# MCU.net
KiCad netlist of a schematic drawn in Altium Designer
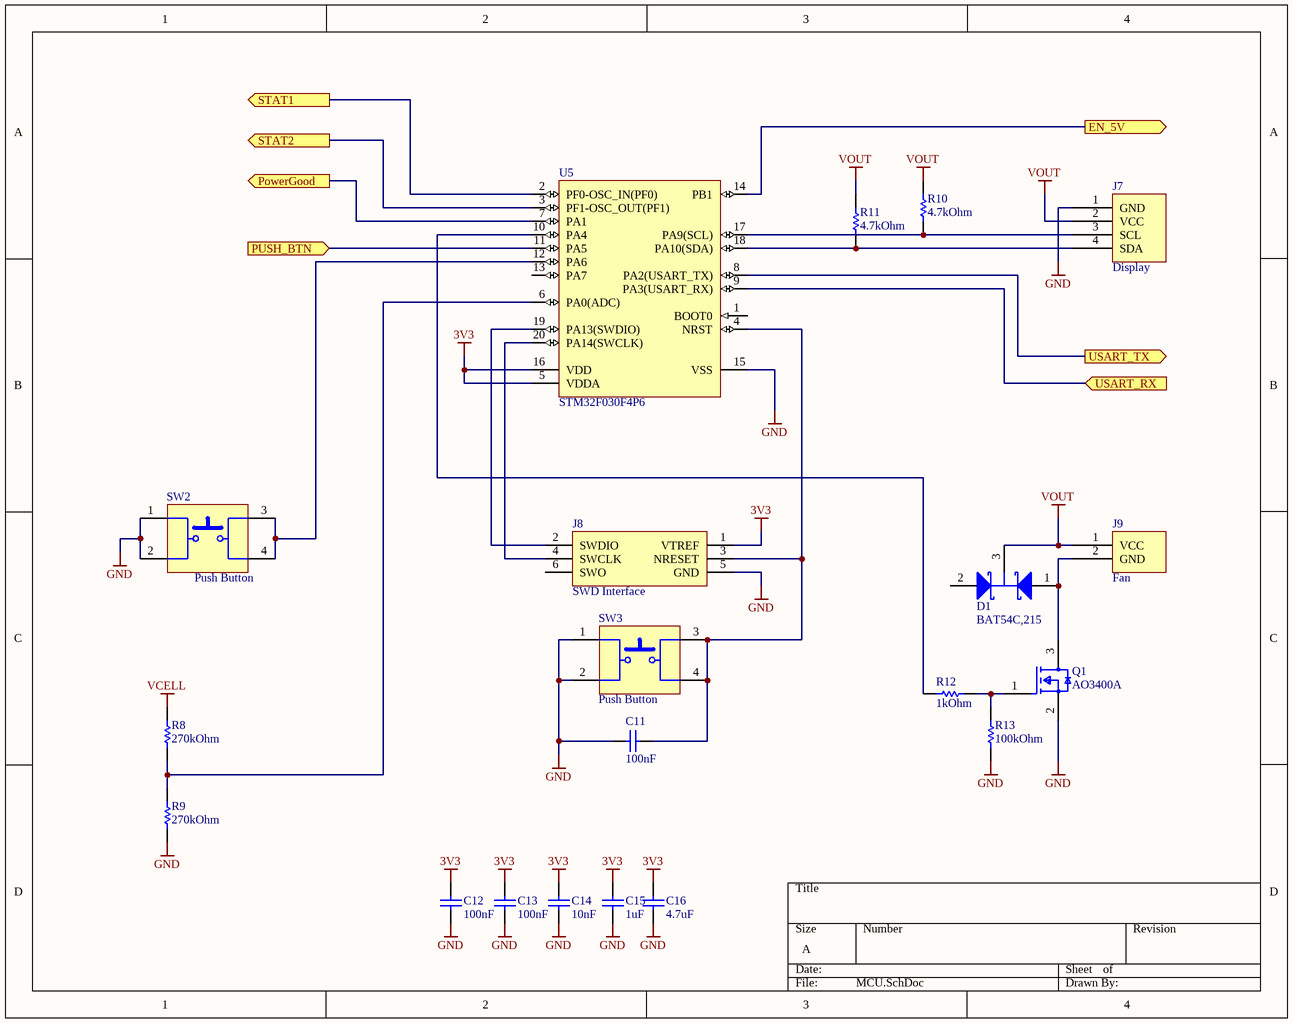
[diagram p0: MCU.SchDoc]

(export (version "E")
  (design (tool "Eeschema 10.0.6"))
  (components
    (comp (ref "C11")
      (value "100nF")
      (footprint "CAP_0804")
      (fields
        (field (name "TOLERANCE") "10%")
        (field (name "PARTNUMBER") "1206GC102KAT1A")
        (field (name "MANUFACTURER") "AVX")
      )
      (libsource (lib "Schlib") (part "CAP_100NF"))
    )
    (comp (ref "C12")
      (value "100nF")
      (footprint "CAP_0804")
      (fields
        (field (name "TOLERANCE") "10%")
        (field (name "PARTNUMBER") "1206GC102KAT1A")
        (field (name "MANUFACTURER") "AVX")
      )
      (libsource (lib "Schlib") (part "CAP_100NF"))
    )
    (comp (ref "C13")
      (value "100nF")
      (footprint "CAP_0804")
      (fields
        (field (name "TOLERANCE") "10%")
        (field (name "PARTNUMBER") "1206GC102KAT1A")
        (field (name "MANUFACTURER") "AVX")
      )
      (libsource (lib "Schlib") (part "CAP_100NF"))
    )
    (comp (ref "C14")
      (value "10nF")
      (footprint "CAP_0804")
      (fields
        (field (name "TOLERANCE") "10%")
        (field (name "PARTNUMBER") "1206GC102KAT1A")
        (field (name "MANUFACTURER") "AVX")
      )
      (libsource (lib "Schlib") (part "CAP_10NF"))
    )
    (comp (ref "C15")
      (value "1uF")
      (footprint "CAP_0804")
      (fields
        (field (name "TOLERANCE") "10%")
        (field (name "PARTNUMBER") "1206GC102KAT1A")
        (field (name "MANUFACTURER") "AVX")
      )
      (libsource (lib "Schlib") (part "CAP_1UF"))
    )
    (comp (ref "C16")
      (value "4.7uF")
      (footprint "CAP_0804")
      (fields
        (field (name "TOLERANCE") "10%")
        (field (name "PARTNUMBER") "1206GC102KAT1A")
        (field (name "MANUFACTURER") "AVX")
      )
      (libsource (lib "Schlib") (part "CAP_4.7UF"))
    )
    (comp (ref "D1")
      (value "BAT54C,215")
      (footprint "SOT23")
      (description "Schottky Barrier Diode, 30 V, 3-Pin SOT23, RoHS, Tape and Reel")
      (fields (field (name "MANUFACTURER") "NXP Semiconductors"))
      (libsource (lib "Schlib") (part "DIODE_BAT54C"))
    )
    (comp (ref "J7")
      (value "Display")
      (footprint "OLED_DISPLAY")
      (fields (field (name "MANUFACTURER") "Samtec") (field (name "PARTNUMBER") "MMS-104-01-T-SV"))
      (libsource (lib "Schlib") (part "Oled Display"))
    )
    (comp (ref "J8")
      (value "SWD Interface")
      (footprint "J-Link_6-pin_Needle_Adapter")
      (description "J-Link 6-pin Needle Adapter")
      (libsource (lib "Schlib") (part "J-Link_6-pin_Needle_Adapter"))
    )
    (comp (ref "J9")
      (value "Fan")
      (footprint "FAN_CONNECTOR")
      (fields (field (name "MANUFACTURER") "Samtec") (field (name "PARTNUMBER") "MMS-104-01-T-SV"))
      (libsource (lib "Schlib") (part "FAN"))
    )
    (comp (ref "Q1")
      (value "AO3400A")
      (footprint "SOT23")
      (description "MOSFET N-CH 30V 5.7A SOT23")
      (libsource (lib "Schlib") (part "MOSFET_AO3400A"))
    )
    (comp (ref "R8")
      (value "270kOhm")
      (footprint "RES_0804")
      (fields (field (name "PART NUMBER") "CRCW120647K0FKEA") (field (name "MANUFACTURER") "Vishay Dale"))
      (libsource (lib "Schlib") (part "RES_270K"))
    )
    (comp (ref "R9")
      (value "270kOhm")
      (footprint "RES_0804")
      (fields (field (name "PART NUMBER") "CRCW120647K0FKEA") (field (name "MANUFACTURER") "Vishay Dale"))
      (libsource (lib "Schlib") (part "RES_270K"))
    )
    (comp (ref "R10")
      (value "4.7kOhm")
      (footprint "RES_0804")
      (fields (field (name "PART NUMBER") "CRCW120647K0FKEA") (field (name "MANUFACTURER") "Vishay Dale"))
      (libsource (lib "Schlib") (part "RES_4.7K"))
    )
    (comp (ref "R11")
      (value "4.7kOhm")
      (footprint "RES_0804")
      (fields (field (name "PART NUMBER") "CRCW120647K0FKEA") (field (name "MANUFACTURER") "Vishay Dale"))
      (libsource (lib "Schlib") (part "RES_4.7K"))
    )
    (comp (ref "R12")
      (value "1kOhm")
      (footprint "RES_0804")
      (fields (field (name "PART NUMBER") "CRCW120647K0FKEA") (field (name "MANUFACTURER") "Vishay Dale"))
      (libsource (lib "Schlib") (part "RES_1K"))
    )
    (comp (ref "R13")
      (value "100kOhm")
      (footprint "RES_0804")
      (fields (field (name "PART NUMBER") "CRCW120647K0FKEA") (field (name "MANUFACTURER") "Vishay Dale"))
      (libsource (lib "Schlib") (part "RES_100K"))
    )
    (comp (ref "SW2")
      (value "Push Button")
      (footprint "SWITCH")
      (description "Micro Miniature Push Button Switch FSM JSM, 50 mA, -35 to 85 degC, 4-Pin SMD, RoHS, Tape and Reel")
      (fields (field (name "MANUFACTURER") "TE Connectivity"))
      (libsource (lib "Schlib") (part "SWITCH"))
    )
    (comp (ref "SW3")
      (value "Push Button")
      (footprint "SWITCH")
      (description "Micro Miniature Push Button Switch FSM JSM, 50 mA, -35 to 85 degC, 4-Pin SMD, RoHS, Tape and Reel")
      (fields (field (name "MANUFACTURER") "TE Connectivity"))
      (libsource (lib "Schlib") (part "SWITCH"))
    )
    (comp (ref "U5")
      (value "STM32F030F4P6")
      (footprint "STM32F030")
      (libsource (lib "Schlib") (part "STM32F030"))
    )
  )
  (nets
    (net (code "1") (name "/EN_5V") (class "Default")
      (node (ref "U5") (pin "14") (pinfunction "PB1_14") (pintype "bidirectional"))
    )
    (net (code "2") (name "/PUSH_BTN") (class "Default")
      (node (ref "U5") (pin "11") (pinfunction "PA5_11") (pintype "bidirectional"))
    )
    (net (code "3") (name "/PowerGood") (class "Default")
      (node (ref "U5") (pin "7") (pinfunction "PA1_7") (pintype "bidirectional"))
    )
    (net (code "4") (name "/STAT1") (class "Default")
      (node (ref "U5") (pin "2") (pinfunction "PF0-OSC_IN(PF0)_2") (pintype "bidirectional"))
    )
    (net (code "5") (name "/STAT2") (class "Default")
      (node (ref "U5") (pin "3") (pinfunction "PF1-OSC_OUT(PF1)_3") (pintype "bidirectional"))
    )
    (net (code "6") (name "/USART_RX") (class "Default")
      (node (ref "U5") (pin "9") (pinfunction "PA3(USART_RX)_9") (pintype "bidirectional"))
    )
    (net (code "7") (name "/USART_TX") (class "Default")
      (node (ref "U5") (pin "8") (pinfunction "PA2(USART_TX)_8") (pintype "bidirectional"))
    )
    (net (code "8") (name "3V3") (class "Default")
      (node (ref "C12") (pin "2") (pinfunction "2_2") (pintype "passive"))
      (node (ref "C13") (pin "2") (pinfunction "2_2") (pintype "passive"))
      (node (ref "C14") (pin "2") (pinfunction "2_2") (pintype "passive"))
      (node (ref "C15") (pin "2") (pinfunction "2_2") (pintype "passive"))
      (node (ref "C16") (pin "2") (pinfunction "2_2") (pintype "passive"))
      (node (ref "J8") (pin "1") (pinfunction "VTREF_1") (pintype "passive"))
      (node (ref "U5") (pin "16") (pinfunction "VDD_16") (pintype "power_in"))
      (node (ref "U5") (pin "5") (pinfunction "VDDA_5") (pintype "power_in"))
    )
    (net (code "9") (name "GND") (class "Default")
      (node (ref "C11") (pin "1") (pinfunction "1_1") (pintype "passive"))
      (node (ref "C12") (pin "1") (pinfunction "1_1") (pintype "passive"))
      (node (ref "C13") (pin "1") (pinfunction "1_1") (pintype "passive"))
      (node (ref "C14") (pin "1") (pinfunction "1_1") (pintype "passive"))
      (node (ref "C15") (pin "1") (pinfunction "1_1") (pintype "passive"))
      (node (ref "C16") (pin "1") (pinfunction "1_1") (pintype "passive"))
      (node (ref "J7") (pin "1") (pinfunction "GND_1") (pintype "passive"))
      (node (ref "J8") (pin "5") (pinfunction "GND_5") (pintype "passive"))
      (node (ref "Q1") (pin "2") (pinfunction "S_2") (pintype "passive"))
      (node (ref "R13") (pin "1") (pinfunction "1_1") (pintype "passive"))
      (node (ref "R9") (pin "1") (pinfunction "1_1") (pintype "passive"))
      (node (ref "SW2") (pin "1") (pinfunction "1_1") (pintype "passive"))
      (node (ref "SW2") (pin "2") (pinfunction "2_2") (pintype "passive"))
      (node (ref "SW3") (pin "1") (pinfunction "1_1") (pintype "passive"))
      (node (ref "SW3") (pin "2") (pinfunction "2_2") (pintype "passive"))
      (node (ref "U5") (pin "15") (pinfunction "VSS_15") (pintype "power_in"))
    )
    (net (code "10") (name "Net-(J7-SCL)") (class "Default")
      (node (ref "J7") (pin "3") (pinfunction "SCL_3") (pintype "passive"))
      (node (ref "R10") (pin "1") (pinfunction "1_1") (pintype "passive"))
      (node (ref "U5") (pin "17") (pinfunction "PA9(SCL)_17") (pintype "bidirectional"))
    )
    (net (code "11") (name "Net-(J7-SDA)") (class "Default")
      (node (ref "J7") (pin "4") (pinfunction "SDA_4") (pintype "passive"))
      (node (ref "R11") (pin "1") (pinfunction "1_1") (pintype "passive"))
      (node (ref "U5") (pin "18") (pinfunction "PA10(SDA)_18") (pintype "bidirectional"))
    )
    (net (code "12") (name "Net-(J8-NRESET)") (class "Default")
      (node (ref "C11") (pin "2") (pinfunction "2_2") (pintype "passive"))
      (node (ref "J8") (pin "3") (pinfunction "NRESET_3") (pintype "passive"))
      (node (ref "SW3") (pin "3") (pinfunction "3_3") (pintype "passive"))
      (node (ref "SW3") (pin "4") (pinfunction "4_4") (pintype "passive"))
      (node (ref "U5") (pin "4") (pinfunction "NRST_4") (pintype "bidirectional"))
    )
    (net (code "13") (name "Net-(J8-SWCLK)") (class "Default")
      (node (ref "J8") (pin "4") (pinfunction "SWCLK_4") (pintype "passive"))
      (node (ref "U5") (pin "20") (pinfunction "PA14(SWCLK)_20") (pintype "bidirectional"))
    )
    (net (code "14") (name "Net-(J8-SWDIO)") (class "Default")
      (node (ref "J8") (pin "2") (pinfunction "SWDIO_2") (pintype "passive"))
      (node (ref "U5") (pin "19") (pinfunction "PA13(SWDIO)_19") (pintype "bidirectional"))
    )
    (net (code "15") (name "Net-(J9-GND)") (class "Default")
      (node (ref "D1") (pin "1") (pinfunction "A_1") (pintype "passive"))
      (node (ref "J9") (pin "2") (pinfunction "GND_2") (pintype "passive"))
      (node (ref "Q1") (pin "3") (pinfunction "D_3") (pintype "passive"))
    )
    (net (code "16") (name "Net-(Q1-G)") (class "Default")
      (node (ref "Q1") (pin "1") (pinfunction "G_1") (pintype "passive"))
      (node (ref "R12") (pin "2") (pinfunction "2_2") (pintype "passive"))
      (node (ref "R13") (pin "2") (pinfunction "2_2") (pintype "passive"))
    )
    (net (code "17") (name "Net-(U5-PA0(ADC))") (class "Default")
      (node (ref "R8") (pin "1") (pinfunction "1_1") (pintype "passive"))
      (node (ref "R9") (pin "2") (pinfunction "2_2") (pintype "passive"))
      (node (ref "U5") (pin "6") (pinfunction "PA0(ADC)_6") (pintype "bidirectional"))
    )
    (net (code "18") (name "Net-(U5-PA4)") (class "Default")
      (node (ref "R12") (pin "1") (pinfunction "1_1") (pintype "passive"))
      (node (ref "U5") (pin "10") (pinfunction "PA4_10") (pintype "bidirectional"))
    )
    (net (code "19") (name "Net-(U5-PA6)") (class "Default")
      (node (ref "SW2") (pin "3") (pinfunction "3_3") (pintype "passive"))
      (node (ref "SW2") (pin "4") (pinfunction "4_4") (pintype "passive"))
      (node (ref "U5") (pin "12") (pinfunction "PA6_12") (pintype "bidirectional"))
    )
    (net (code "20") (name "VCELL") (class "Default")
      (node (ref "R8") (pin "2") (pinfunction "2_2") (pintype "passive"))
    )
    (net (code "21") (name "VOUT") (class "Default")
      (node (ref "D1") (pin "3") (pinfunction "K_3") (pintype "passive"))
      (node (ref "J7") (pin "2") (pinfunction "VCC_2") (pintype "passive"))
      (node (ref "J9") (pin "1") (pinfunction "VCC_1") (pintype "passive"))
      (node (ref "R10") (pin "2") (pinfunction "2_2") (pintype "passive"))
      (node (ref "R11") (pin "2") (pinfunction "2_2") (pintype "passive"))
    )
    (net (code "22") (name "unconnected-(D1-A-Pad2)") (class "Default")
      (node (ref "D1") (pin "2") (pinfunction "A_2") (pintype "passive"))
    )
    (net (code "23") (name "unconnected-(J8-SWO-Pad6)") (class "Default")
      (node (ref "J8") (pin "6") (pinfunction "SWO_6") (pintype "passive"))
    )
    (net (code "24") (name "unconnected-(U5-BOOT0-Pad1)") (class "Default")
      (node (ref "U5") (pin "1") (pinfunction "BOOT0_1") (pintype "input"))
    )
    (net (code "25") (name "unconnected-(U5-PA7-Pad13)") (class "Default")
      (node (ref "U5") (pin "13") (pinfunction "PA7_13") (pintype "bidirectional"))
    )
  )
)
